# 40Ortho.net
KiCad netlist of a schematic drawn in EAGLE
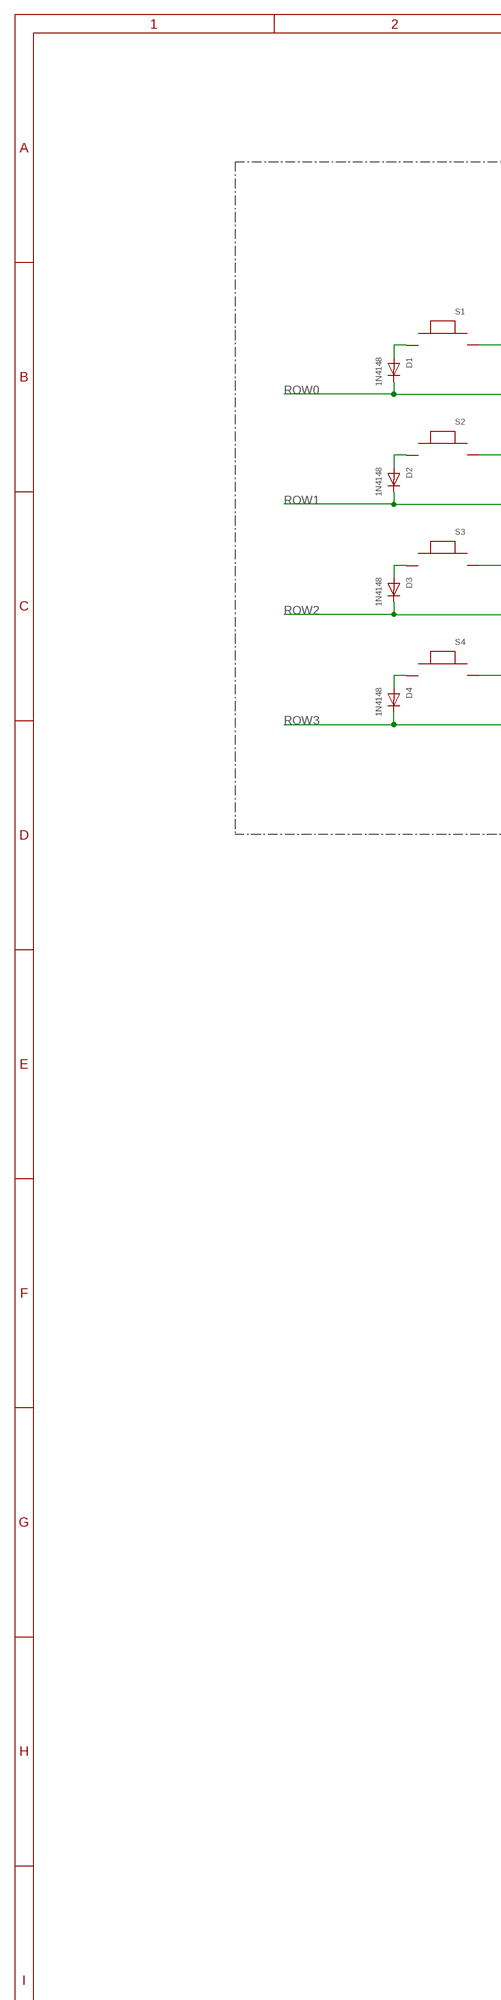
[diagram p0: schematic, sheet 1, part 1 of 2]
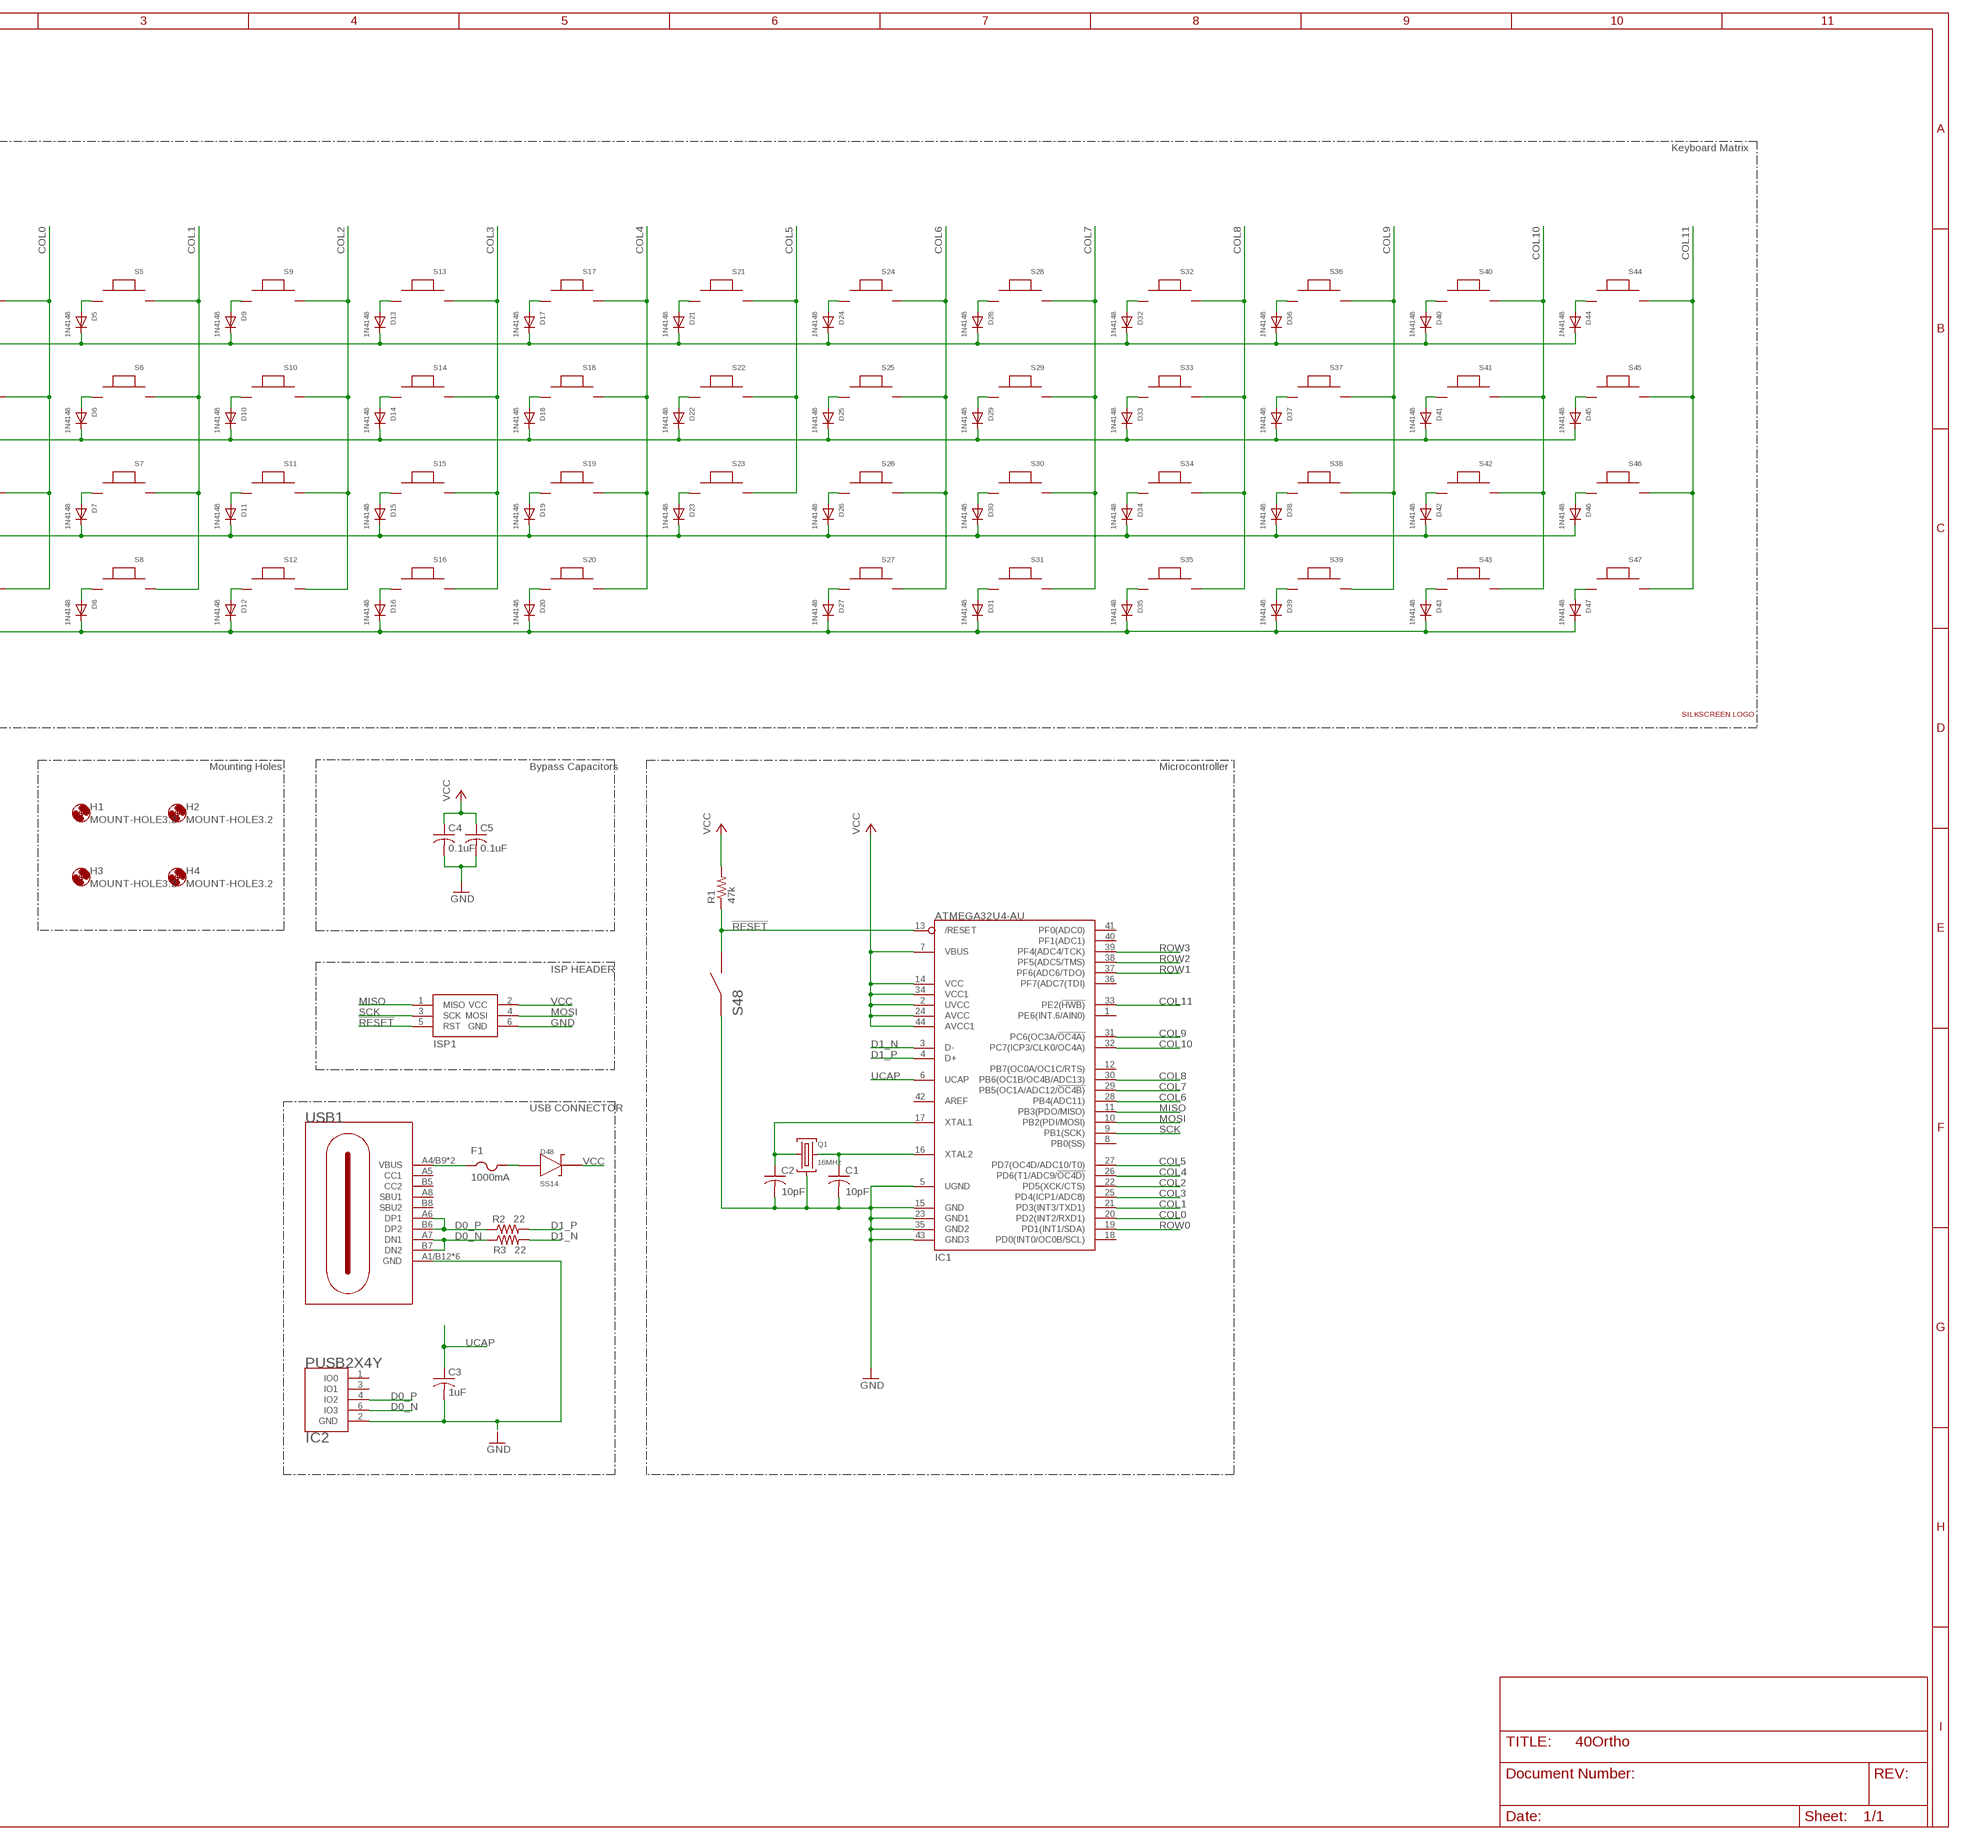
[diagram p1: schematic, sheet 1, part 2 of 2]

(export (version "E")
  (design (tool "Eeschema 10.0.6"))
  (components
    (comp (ref "C1")
      (value "10pF")
      (footprint "eagle-import:C0805")
      (libsource (lib "eagle-import") (part "C-USC0805"))
    )
    (comp (ref "C2")
      (value "10pF")
      (footprint "eagle-import:C0805")
      (libsource (lib "eagle-import") (part "C-USC0805"))
    )
    (comp (ref "C3")
      (value "1uF")
      (footprint "eagle-import:C0805")
      (libsource (lib "eagle-import") (part "C-USC0805"))
    )
    (comp (ref "C4")
      (value "0.1uF")
      (footprint "eagle-import:C0805")
      (libsource (lib "eagle-import") (part "C-USC0805"))
    )
    (comp (ref "C5")
      (value "0.1uF")
      (footprint "eagle-import:C0805")
      (libsource (lib "eagle-import") (part "C-USC0805"))
    )
    (comp (ref "D1")
      (value "1N4148")
      (footprint "eagle-import:SOD-323F")
      (fields (field (name "SPICEPREFIX") "D"))
      (libsource (lib "eagle-import") (part "DIODESOD-323F"))
    )
    (comp (ref "D2")
      (value "1N4148")
      (footprint "eagle-import:SOD-323F")
      (libsource (lib "eagle-import") (part "DIODESOD-323F"))
    )
    (comp (ref "D3")
      (value "1N4148")
      (footprint "eagle-import:SOD-323F")
      (libsource (lib "eagle-import") (part "DIODESOD-323F"))
    )
    (comp (ref "D4")
      (value "1N4148")
      (footprint "eagle-import:SOD-323F")
      (libsource (lib "eagle-import") (part "DIODESOD-323F"))
    )
    (comp (ref "D5")
      (value "1N4148")
      (footprint "eagle-import:SOD-323F")
      (libsource (lib "eagle-import") (part "DIODESOD-323F"))
    )
    (comp (ref "D6")
      (value "1N4148")
      (footprint "eagle-import:SOD-323F")
      (fields (field (name "SPICEPREFIX") "D"))
      (libsource (lib "eagle-import") (part "DIODESOD-323F"))
    )
    (comp (ref "D7")
      (value "1N4148")
      (footprint "eagle-import:SOD-323F")
      (libsource (lib "eagle-import") (part "DIODESOD-323F"))
    )
    (comp (ref "D8")
      (value "1N4148")
      (footprint "eagle-import:SOD-323F")
      (libsource (lib "eagle-import") (part "DIODESOD-323F"))
    )
    (comp (ref "D9")
      (value "1N4148")
      (footprint "eagle-import:SOD-323F")
      (libsource (lib "eagle-import") (part "DIODESOD-323F"))
    )
    (comp (ref "D10")
      (value "1N4148")
      (footprint "eagle-import:SOD-323F")
      (libsource (lib "eagle-import") (part "DIODESOD-323F"))
    )
    (comp (ref "D11")
      (value "1N4148")
      (footprint "eagle-import:SOD-323F")
      (libsource (lib "eagle-import") (part "DIODESOD-323F"))
    )
    (comp (ref "D12")
      (value "1N4148")
      (footprint "eagle-import:SOD-323F")
      (libsource (lib "eagle-import") (part "DIODESOD-323F"))
    )
    (comp (ref "D13")
      (value "1N4148")
      (footprint "eagle-import:SOD-323F")
      (libsource (lib "eagle-import") (part "DIODESOD-323F"))
    )
    (comp (ref "D14")
      (value "1N4148")
      (footprint "eagle-import:SOD-323F")
      (libsource (lib "eagle-import") (part "DIODESOD-323F"))
    )
    (comp (ref "D15")
      (value "1N4148")
      (footprint "eagle-import:SOD-323F")
      (libsource (lib "eagle-import") (part "DIODESOD-323F"))
    )
    (comp (ref "D16")
      (value "1N4148")
      (footprint "eagle-import:SOD-323F")
      (libsource (lib "eagle-import") (part "DIODESOD-323F"))
    )
    (comp (ref "D17")
      (value "1N4148")
      (footprint "eagle-import:SOD-323F")
      (libsource (lib "eagle-import") (part "DIODESOD-323F"))
    )
    (comp (ref "D18")
      (value "1N4148")
      (footprint "eagle-import:SOD-323F")
      (libsource (lib "eagle-import") (part "DIODESOD-323F"))
    )
    (comp (ref "D19")
      (value "1N4148")
      (footprint "eagle-import:SOD-323F")
      (libsource (lib "eagle-import") (part "DIODESOD-323F"))
    )
    (comp (ref "D20")
      (value "1N4148")
      (footprint "eagle-import:SOD-323F")
      (libsource (lib "eagle-import") (part "DIODESOD-323F"))
    )
    (comp (ref "D21")
      (value "1N4148")
      (footprint "eagle-import:SOD-323F")
      (libsource (lib "eagle-import") (part "DIODESOD-323F"))
    )
    (comp (ref "D22")
      (value "1N4148")
      (footprint "eagle-import:SOD-323F")
      (libsource (lib "eagle-import") (part "DIODESOD-323F"))
    )
    (comp (ref "D23")
      (value "1N4148")
      (footprint "eagle-import:SOD-323F")
      (libsource (lib "eagle-import") (part "DIODESOD-323F"))
    )
    (comp (ref "D24")
      (value "1N4148")
      (footprint "eagle-import:SOD-323F")
      (libsource (lib "eagle-import") (part "DIODESOD-323F"))
    )
    (comp (ref "D25")
      (value "1N4148")
      (footprint "eagle-import:SOD-323F")
      (libsource (lib "eagle-import") (part "DIODESOD-323F"))
    )
    (comp (ref "D26")
      (value "1N4148")
      (footprint "eagle-import:SOD-323F")
      (libsource (lib "eagle-import") (part "DIODESOD-323F"))
    )
    (comp (ref "D27")
      (value "1N4148")
      (footprint "eagle-import:SOD-323F")
      (libsource (lib "eagle-import") (part "DIODESOD-323F"))
    )
    (comp (ref "D28")
      (value "1N4148")
      (footprint "eagle-import:SOD-323F")
      (libsource (lib "eagle-import") (part "DIODESOD-323F"))
    )
    (comp (ref "D29")
      (value "1N4148")
      (footprint "eagle-import:SOD-323F")
      (libsource (lib "eagle-import") (part "DIODESOD-323F"))
    )
    (comp (ref "D30")
      (value "1N4148")
      (footprint "eagle-import:SOD-323F")
      (libsource (lib "eagle-import") (part "DIODESOD-323F"))
    )
    (comp (ref "D31")
      (value "1N4148")
      (footprint "eagle-import:SOD-323F")
      (libsource (lib "eagle-import") (part "DIODESOD-323F"))
    )
    (comp (ref "D32")
      (value "1N4148")
      (footprint "eagle-import:SOD-323F")
      (libsource (lib "eagle-import") (part "DIODESOD-323F"))
    )
    (comp (ref "D33")
      (value "1N4148")
      (footprint "eagle-import:SOD-323F")
      (libsource (lib "eagle-import") (part "DIODESOD-323F"))
    )
    (comp (ref "D34")
      (value "1N4148")
      (footprint "eagle-import:SOD-323F")
      (libsource (lib "eagle-import") (part "DIODESOD-323F"))
    )
    (comp (ref "D35")
      (value "1N4148")
      (footprint "eagle-import:SOD-323F")
      (libsource (lib "eagle-import") (part "DIODESOD-323F"))
    )
    (comp (ref "D36")
      (value "1N4148")
      (footprint "eagle-import:SOD-323F")
      (libsource (lib "eagle-import") (part "DIODESOD-323F"))
    )
    (comp (ref "D37")
      (value "1N4148")
      (footprint "eagle-import:SOD-323F")
      (libsource (lib "eagle-import") (part "DIODESOD-323F"))
    )
    (comp (ref "D38")
      (value "1N4148")
      (footprint "eagle-import:SOD-323F")
      (libsource (lib "eagle-import") (part "DIODESOD-323F"))
    )
    (comp (ref "D39")
      (value "1N4148")
      (footprint "eagle-import:SOD-323F")
      (libsource (lib "eagle-import") (part "DIODESOD-323F"))
    )
    (comp (ref "D40")
      (value "1N4148")
      (footprint "eagle-import:SOD-323F")
      (libsource (lib "eagle-import") (part "DIODESOD-323F"))
    )
    (comp (ref "D41")
      (value "1N4148")
      (footprint "eagle-import:SOD-323F")
      (libsource (lib "eagle-import") (part "DIODESOD-323F"))
    )
    (comp (ref "D42")
      (value "1N4148")
      (footprint "eagle-import:SOD-323F")
      (libsource (lib "eagle-import") (part "DIODESOD-323F"))
    )
    (comp (ref "D43")
      (value "1N4148")
      (footprint "eagle-import:SOD-323F")
      (libsource (lib "eagle-import") (part "DIODESOD-323F"))
    )
    (comp (ref "D44")
      (value "1N4148")
      (footprint "eagle-import:SOD-323F")
      (libsource (lib "eagle-import") (part "DIODESOD-323F"))
    )
    (comp (ref "D45")
      (value "1N4148")
      (footprint "eagle-import:SOD-323F")
      (libsource (lib "eagle-import") (part "DIODESOD-323F"))
    )
    (comp (ref "D46")
      (value "1N4148")
      (footprint "eagle-import:SOD-323F")
      (libsource (lib "eagle-import") (part "DIODESOD-323F"))
    )
    (comp (ref "D47")
      (value "1N4148")
      (footprint "eagle-import:SOD-323F")
      (libsource (lib "eagle-import") (part "DIODESOD-323F"))
    )
    (comp (ref "D48")
      (value "SS14")
      (footprint "eagle-import:DO-214AC")
      (libsource (lib "eagle-import") (part "SS14"))
    )
    (comp (ref "F1")
      (value "1000mA")
      (footprint "eagle-import:R1206")
      (libsource (lib "eagle-import") (part "PTCFUSE-1206"))
    )
    (comp (ref "H1")
      (value "MOUNT-HOLE3.2")
      (footprint "eagle-import:3,2")
      (libsource (lib "eagle-import") (part "MOUNT-HOLE3.2"))
    )
    (comp (ref "H2")
      (value "MOUNT-HOLE3.2")
      (footprint "eagle-import:3,2")
      (libsource (lib "eagle-import") (part "MOUNT-HOLE3.2"))
    )
    (comp (ref "H3")
      (value "MOUNT-HOLE3.2")
      (footprint "eagle-import:3,2")
      (libsource (lib "eagle-import") (part "MOUNT-HOLE3.2"))
    )
    (comp (ref "H4")
      (value "MOUNT-HOLE3.2")
      (footprint "eagle-import:3,2")
      (libsource (lib "eagle-import") (part "MOUNT-HOLE3.2"))
    )
    (comp (ref "IC1")
      (value "ATMEGA32U4-AU")
      (footprint "eagle-import:TQFP44")
      (libsource (lib "eagle-import") (part "ATMEGA32U4-AU"))
    )
    (comp (ref "IC2")
      (value "PUSB2X4Y")
      (footprint "eagle-import:SOT363")
      (libsource (lib "eagle-import") (part "PUSB2X4Y"))
    )
    (comp (ref "ISP1")
      (value "AVRISP")
      (footprint "eagle-import:AVRISP")
      (libsource (lib "eagle-import") (part "AVRISP"))
    )
    (comp (ref "Q1")
      (value "16MHz")
      (footprint "eagle-import:TSX-3225")
      (libsource (lib "eagle-import") (part "TSX-3225"))
    )
    (comp (ref "R1")
      (value "47k")
      (footprint "eagle-import:R0805")
      (libsource (lib "eagle-import") (part "R-US_R0805"))
    )
    (comp (ref "R2")
      (value "22")
      (footprint "eagle-import:R0805")
      (libsource (lib "eagle-import") (part "R-US_R0805"))
    )
    (comp (ref "R3")
      (value "22")
      (footprint "eagle-import:R0805")
      (libsource (lib "eagle-import") (part "R-US_R0805"))
    )
    (comp (ref "S1")
      (value "MX_SMD_1U")
      (footprint "eagle-import:MX_SMD")
      (libsource (lib "eagle-import") (part "MX_SMD_1U"))
    )
    (comp (ref "S2")
      (value "MX_SMD_1U")
      (footprint "eagle-import:MX_SMD")
      (libsource (lib "eagle-import") (part "MX_SMD_1U"))
    )
    (comp (ref "S3")
      (value "MX_SMD_1U")
      (footprint "eagle-import:MX_SMD")
      (libsource (lib "eagle-import") (part "MX_SMD_1U"))
    )
    (comp (ref "S4")
      (value "MX_SMD_1U")
      (footprint "eagle-import:MX_SMD")
      (libsource (lib "eagle-import") (part "MX_SMD_1U"))
    )
    (comp (ref "S5")
      (value "MX_SMD_1U")
      (footprint "eagle-import:MX_SMD")
      (libsource (lib "eagle-import") (part "MX_SMD_1U"))
    )
    (comp (ref "S6")
      (value "MX_SMD_1U")
      (footprint "eagle-import:MX_SMD")
      (libsource (lib "eagle-import") (part "MX_SMD_1U"))
    )
    (comp (ref "S7")
      (value "MX_SMD_1U")
      (footprint "eagle-import:MX_SMD")
      (libsource (lib "eagle-import") (part "MX_SMD_1U"))
    )
    (comp (ref "S8")
      (value "MX_SMD_1U")
      (footprint "eagle-import:MX_SMD")
      (libsource (lib "eagle-import") (part "MX_SMD_1U"))
    )
    (comp (ref "S9")
      (value "MX_SMD_1U")
      (footprint "eagle-import:MX_SMD")
      (libsource (lib "eagle-import") (part "MX_SMD_1U"))
    )
    (comp (ref "S10")
      (value "MX_SMD_1U")
      (footprint "eagle-import:MX_SMD")
      (libsource (lib "eagle-import") (part "MX_SMD_1U"))
    )
    (comp (ref "S11")
      (value "MX_SMD_1U")
      (footprint "eagle-import:MX_SMD")
      (libsource (lib "eagle-import") (part "MX_SMD_1U"))
    )
    (comp (ref "S12")
      (value "MX_SMD_1U")
      (footprint "eagle-import:MX_SMD")
      (libsource (lib "eagle-import") (part "MX_SMD_1U"))
    )
    (comp (ref "S13")
      (value "MX_SMD_1U")
      (footprint "eagle-import:MX_SMD")
      (libsource (lib "eagle-import") (part "MX_SMD_1U"))
    )
    (comp (ref "S14")
      (value "MX_SMD_1U")
      (footprint "eagle-import:MX_SMD")
      (libsource (lib "eagle-import") (part "MX_SMD_1U"))
    )
    (comp (ref "S15")
      (value "MX_SMD_1U")
      (footprint "eagle-import:MX_SMD")
      (libsource (lib "eagle-import") (part "MX_SMD_1U"))
    )
    (comp (ref "S16")
      (value "MX_SMD_1U")
      (footprint "eagle-import:MX_SMD")
      (libsource (lib "eagle-import") (part "MX_SMD_1U"))
    )
    (comp (ref "S17")
      (value "MX_SMD_1U")
      (footprint "eagle-import:MX_SMD")
      (libsource (lib "eagle-import") (part "MX_SMD_1U"))
    )
    (comp (ref "S18")
      (value "MX_SMD_1U")
      (footprint "eagle-import:MX_SMD")
      (libsource (lib "eagle-import") (part "MX_SMD_1U"))
    )
    (comp (ref "S19")
      (value "MX_SMD_1U")
      (footprint "eagle-import:MX_SMD")
      (libsource (lib "eagle-import") (part "MX_SMD_1U"))
    )
    (comp (ref "S20")
      (value "MX_SMD_1U")
      (footprint "eagle-import:MX_SMD")
      (libsource (lib "eagle-import") (part "MX_SMD_1U"))
    )
    (comp (ref "S21")
      (value "MX_SMD_1U")
      (footprint "eagle-import:MX_SMD")
      (libsource (lib "eagle-import") (part "MX_SMD_1U"))
    )
    (comp (ref "S22")
      (value "MX_SMD_1U")
      (footprint "eagle-import:MX_SMD")
      (libsource (lib "eagle-import") (part "MX_SMD_1U"))
    )
    (comp (ref "S23")
      (value "MX_SMD_1U")
      (footprint "eagle-import:MX_SMD")
      (libsource (lib "eagle-import") (part "MX_SMD_1U"))
    )
    (comp (ref "S24")
      (value "MX_SMD_1U")
      (footprint "eagle-import:MX_SMD")
      (libsource (lib "eagle-import") (part "MX_SMD_1U"))
    )
    (comp (ref "S25")
      (value "MX_SMD_1U")
      (footprint "eagle-import:MX_SMD")
      (libsource (lib "eagle-import") (part "MX_SMD_1U"))
    )
    (comp (ref "S26")
      (value "MX_SMD_1U")
      (footprint "eagle-import:MX_SMD")
      (libsource (lib "eagle-import") (part "MX_SMD_1U"))
    )
    (comp (ref "S27")
      (value "MX_SMD_2UH")
      (footprint "eagle-import:MX_SMD2U")
      (libsource (lib "eagle-import") (part "MX_SMD_2UH"))
    )
    (comp (ref "S28")
      (value "MX_SMD_1U")
      (footprint "eagle-import:MX_SMD")
      (libsource (lib "eagle-import") (part "MX_SMD_1U"))
    )
    (comp (ref "S29")
      (value "MX_SMD_1U")
      (footprint "eagle-import:MX_SMD")
      (libsource (lib "eagle-import") (part "MX_SMD_1U"))
    )
    (comp (ref "S30")
      (value "MX_SMD_1U")
      (footprint "eagle-import:MX_SMD")
      (libsource (lib "eagle-import") (part "MX_SMD_1U"))
    )
    (comp (ref "S31")
      (value "MX_SMD_1U")
      (footprint "eagle-import:MX_SMD")
      (libsource (lib "eagle-import") (part "MX_SMD_1U"))
    )
    (comp (ref "S32")
      (value "MX_SMD_1U")
      (footprint "eagle-import:MX_SMD")
      (libsource (lib "eagle-import") (part "MX_SMD_1U"))
    )
    (comp (ref "S33")
      (value "MX_SMD_1U")
      (footprint "eagle-import:MX_SMD")
      (libsource (lib "eagle-import") (part "MX_SMD_1U"))
    )
    (comp (ref "S34")
      (value "MX_SMD_1U")
      (footprint "eagle-import:MX_SMD")
      (libsource (lib "eagle-import") (part "MX_SMD_1U"))
    )
    (comp (ref "S35")
      (value "MX_SMD_1U")
      (footprint "eagle-import:MX_SMD")
      (libsource (lib "eagle-import") (part "MX_SMD_1U"))
    )
    (comp (ref "S36")
      (value "MX_SMD_1U")
      (footprint "eagle-import:MX_SMD")
      (libsource (lib "eagle-import") (part "MX_SMD_1U"))
    )
    (comp (ref "S37")
      (value "MX_SMD_1U")
      (footprint "eagle-import:MX_SMD")
      (libsource (lib "eagle-import") (part "MX_SMD_1U"))
    )
    (comp (ref "S38")
      (value "MX_SMD_1U")
      (footprint "eagle-import:MX_SMD")
      (libsource (lib "eagle-import") (part "MX_SMD_1U"))
    )
    (comp (ref "S39")
      (value "MX_SMD_1U")
      (footprint "eagle-import:MX_SMD")
      (libsource (lib "eagle-import") (part "MX_SMD_1U"))
    )
    (comp (ref "S40")
      (value "MX_SMD_1U")
      (footprint "eagle-import:MX_SMD")
      (libsource (lib "eagle-import") (part "MX_SMD_1U"))
    )
    (comp (ref "S41")
      (value "MX_SMD_1U")
      (footprint "eagle-import:MX_SMD")
      (libsource (lib "eagle-import") (part "MX_SMD_1U"))
    )
    (comp (ref "S42")
      (value "MX_SMD_1U")
      (footprint "eagle-import:MX_SMD")
      (libsource (lib "eagle-import") (part "MX_SMD_1U"))
    )
    (comp (ref "S43")
      (value "MX_SMD_1U")
      (footprint "eagle-import:MX_SMD")
      (libsource (lib "eagle-import") (part "MX_SMD_1U"))
    )
    (comp (ref "S44")
      (value "MX_SMD_1U")
      (footprint "eagle-import:MX_SMD")
      (libsource (lib "eagle-import") (part "MX_SMD_1U"))
    )
    (comp (ref "S45")
      (value "MX_SMD_1U")
      (footprint "eagle-import:MX_SMD")
      (libsource (lib "eagle-import") (part "MX_SMD_1U"))
    )
    (comp (ref "S46")
      (value "MX_SMD_1U")
      (footprint "eagle-import:MX_SMD")
      (libsource (lib "eagle-import") (part "MX_SMD_1U"))
    )
    (comp (ref "S47")
      (value "MX_SMD_1U")
      (footprint "eagle-import:MX_SMD")
      (libsource (lib "eagle-import") (part "MX_SMD_1U"))
    )
    (comp (ref "S48")
      (value "B3U-1000P")
      (footprint "eagle-import:B3U-1000P")
      (libsource (lib "eagle-import") (part "B3U-1000P"))
    )
    (comp (ref "U$1")
      (value "LOGO")
      (footprint "eagle-import:LOGO")
      (libsource (lib "eagle-import") (part "LOGO"))
    )
    (comp (ref "USB1")
      (value "USBC_16PINSMD")
      (footprint "eagle-import:USBC_16PINSMD")
      (libsource (lib "eagle-import") (part "USBC_16PINSMD"))
    )
  )
  (nets
    (net (code "1") (name "/COL0") (class "Default")
      (node (ref "IC1") (pin "20") (pinfunction "PD2(INT2/RXD1)_20") (pintype "bidirectional"))
      (node (ref "S1") (pin "P$2") (pinfunction "P$2_P$2") (pintype "bidirectional"))
      (node (ref "S2") (pin "P$2") (pinfunction "P$2_P$2") (pintype "bidirectional"))
      (node (ref "S3") (pin "P$2") (pinfunction "P$2_P$2") (pintype "bidirectional"))
      (node (ref "S4") (pin "P$2") (pinfunction "P$2_P$2") (pintype "bidirectional"))
    )
    (net (code "2") (name "/COL1") (class "Default")
      (node (ref "IC1") (pin "21") (pinfunction "PD3(INT3/TXD1)_21") (pintype "bidirectional"))
      (node (ref "S5") (pin "P$2") (pinfunction "P$2_P$2") (pintype "bidirectional"))
      (node (ref "S6") (pin "P$2") (pinfunction "P$2_P$2") (pintype "bidirectional"))
      (node (ref "S7") (pin "P$2") (pinfunction "P$2_P$2") (pintype "bidirectional"))
      (node (ref "S8") (pin "P$2") (pinfunction "P$2_P$2") (pintype "bidirectional"))
    )
    (net (code "3") (name "/COL2") (class "Default")
      (node (ref "IC1") (pin "22") (pinfunction "PD5(XCK/CTS)_22") (pintype "bidirectional"))
      (node (ref "S10") (pin "P$2") (pinfunction "P$2_P$2") (pintype "bidirectional"))
      (node (ref "S11") (pin "P$2") (pinfunction "P$2_P$2") (pintype "bidirectional"))
      (node (ref "S12") (pin "P$2") (pinfunction "P$2_P$2") (pintype "bidirectional"))
      (node (ref "S9") (pin "P$2") (pinfunction "P$2_P$2") (pintype "bidirectional"))
    )
    (net (code "4") (name "/COL3") (class "Default")
      (node (ref "IC1") (pin "25") (pinfunction "PD4(ICP1/ADC8)_25") (pintype "bidirectional"))
      (node (ref "S13") (pin "P$2") (pinfunction "P$2_P$2") (pintype "bidirectional"))
      (node (ref "S14") (pin "P$2") (pinfunction "P$2_P$2") (pintype "bidirectional"))
      (node (ref "S15") (pin "P$2") (pinfunction "P$2_P$2") (pintype "bidirectional"))
      (node (ref "S16") (pin "P$2") (pinfunction "P$2_P$2") (pintype "bidirectional"))
    )
    (net (code "5") (name "/COL4") (class "Default")
      (node (ref "IC1") (pin "26") (pinfunction "PD6(T1/ADC9/~{OC4D})_26") (pintype "bidirectional"))
      (node (ref "S17") (pin "P$2") (pinfunction "P$2_P$2") (pintype "bidirectional"))
      (node (ref "S18") (pin "P$2") (pinfunction "P$2_P$2") (pintype "bidirectional"))
      (node (ref "S19") (pin "P$2") (pinfunction "P$2_P$2") (pintype "bidirectional"))
      (node (ref "S20") (pin "P$2") (pinfunction "P$2_P$2") (pintype "bidirectional"))
    )
    (net (code "6") (name "/COL5") (class "Default")
      (node (ref "IC1") (pin "27") (pinfunction "PD7(OC4D/ADC10/T0)_27") (pintype "bidirectional"))
      (node (ref "S21") (pin "P$2") (pinfunction "P$2_P$2") (pintype "bidirectional"))
      (node (ref "S22") (pin "P$2") (pinfunction "P$2_P$2") (pintype "bidirectional"))
      (node (ref "S23") (pin "P$2") (pinfunction "P$2_P$2") (pintype "bidirectional"))
    )
    (net (code "7") (name "/COL6") (class "Default")
      (node (ref "IC1") (pin "28") (pinfunction "PB4(ADC11)_28") (pintype "bidirectional"))
      (node (ref "S24") (pin "P$2") (pinfunction "P$2_P$2") (pintype "bidirectional"))
      (node (ref "S25") (pin "P$2") (pinfunction "P$2_P$2") (pintype "bidirectional"))
      (node (ref "S26") (pin "P$2") (pinfunction "P$2_P$2") (pintype "bidirectional"))
      (node (ref "S27") (pin "P$2") (pinfunction "P$2_P$2") (pintype "bidirectional"))
    )
    (net (code "8") (name "/COL7") (class "Default")
      (node (ref "IC1") (pin "29") (pinfunction "PB5(OC1A/ADC12/~{OC4B})_29") (pintype "bidirectional"))
      (node (ref "S28") (pin "P$2") (pinfunction "P$2_P$2") (pintype "bidirectional"))
      (node (ref "S29") (pin "P$2") (pinfunction "P$2_P$2") (pintype "bidirectional"))
      (node (ref "S30") (pin "P$2") (pinfunction "P$2_P$2") (pintype "bidirectional"))
      (node (ref "S31") (pin "P$2") (pinfunction "P$2_P$2") (pintype "bidirectional"))
    )
    (net (code "9") (name "/COL8") (class "Default")
      (node (ref "IC1") (pin "30") (pinfunction "PB6(OC1B/OC4B/ADC13)_30") (pintype "bidirectional"))
      (node (ref "S32") (pin "P$2") (pinfunction "P$2_P$2") (pintype "bidirectional"))
      (node (ref "S33") (pin "P$2") (pinfunction "P$2_P$2") (pintype "bidirectional"))
      (node (ref "S34") (pin "P$2") (pinfunction "P$2_P$2") (pintype "bidirectional"))
      (node (ref "S35") (pin "P$2") (pinfunction "P$2_P$2") (pintype "bidirectional"))
    )
    (net (code "10") (name "/COL9") (class "Default")
      (node (ref "IC1") (pin "31") (pinfunction "PC6(OC3A/~{OC4A})_31") (pintype "bidirectional"))
      (node (ref "S36") (pin "P$2") (pinfunction "P$2_P$2") (pintype "bidirectional"))
      (node (ref "S37") (pin "P$2") (pinfunction "P$2_P$2") (pintype "bidirectional"))
      (node (ref "S38") (pin "P$2") (pinfunction "P$2_P$2") (pintype "bidirectional"))
      (node (ref "S39") (pin "P$2") (pinfunction "P$2_P$2") (pintype "bidirectional"))
    )
    (net (code "11") (name "/COL10") (class "Default")
      (node (ref "IC1") (pin "32") (pinfunction "PC7(ICP3/CLK0/OC4A)_32") (pintype "bidirectional"))
      (node (ref "S40") (pin "P$2") (pinfunction "P$2_P$2") (pintype "bidirectional"))
      (node (ref "S41") (pin "P$2") (pinfunction "P$2_P$2") (pintype "bidirectional"))
      (node (ref "S42") (pin "P$2") (pinfunction "P$2_P$2") (pintype "bidirectional"))
      (node (ref "S43") (pin "P$2") (pinfunction "P$2_P$2") (pintype "bidirectional"))
    )
    (net (code "12") (name "/COL11") (class "Default")
      (node (ref "IC1") (pin "33") (pinfunction "PE2(~{HWB})_33") (pintype "bidirectional"))
      (node (ref "S44") (pin "P$2") (pinfunction "P$2_P$2") (pintype "bidirectional"))
      (node (ref "S45") (pin "P$2") (pinfunction "P$2_P$2") (pintype "bidirectional"))
      (node (ref "S46") (pin "P$2") (pinfunction "P$2_P$2") (pintype "bidirectional"))
      (node (ref "S47") (pin "P$2") (pinfunction "P$2_P$2") (pintype "bidirectional"))
    )
    (net (code "13") (name "/D0_N") (class "Default")
      (node (ref "IC2") (pin "6") (pinfunction "IO3_6") (pintype "bidirectional"))
      (node (ref "R3") (pin "1") (pinfunction "1_1") (pintype "passive"))
      (node (ref "USB1") (pin "A7") (pinfunction "DN1_A7") (pintype "bidirectional"))
      (node (ref "USB1") (pin "B7") (pinfunction "DN2_B7") (pintype "bidirectional"))
    )
    (net (code "14") (name "/D0_P") (class "Default")
      (node (ref "IC2") (pin "4") (pinfunction "IO2_4") (pintype "bidirectional"))
      (node (ref "R2") (pin "1") (pinfunction "1_1") (pintype "passive"))
      (node (ref "USB1") (pin "A6") (pinfunction "DP1_A6") (pintype "bidirectional"))
      (node (ref "USB1") (pin "B6") (pinfunction "DP2_B6") (pintype "bidirectional"))
    )
    (net (code "15") (name "/D1_N") (class "Default")
      (node (ref "IC1") (pin "3") (pinfunction "D-_3") (pintype "bidirectional"))
      (node (ref "R3") (pin "2") (pinfunction "2_2") (pintype "passive"))
    )
    (net (code "16") (name "/D1_P") (class "Default")
      (node (ref "IC1") (pin "4") (pinfunction "D+_4") (pintype "bidirectional"))
      (node (ref "R2") (pin "2") (pinfunction "2_2") (pintype "passive"))
    )
    (net (code "17") (name "/MISO") (class "Default")
      (node (ref "IC1") (pin "11") (pinfunction "PB3(PDO/MISO)_11") (pintype "bidirectional"))
      (node (ref "ISP1") (pin "1") (pinfunction "MISO_1") (pintype "bidirectional"))
    )
    (net (code "18") (name "/MOSI") (class "Default")
      (node (ref "IC1") (pin "10") (pinfunction "PB2(PDI/MOSI)_10") (pintype "bidirectional"))
      (node (ref "ISP1") (pin "4") (pinfunction "MOSI_4") (pintype "bidirectional"))
    )
    (net (code "19") (name "/ROW0") (class "Default")
      (node (ref "D1") (pin "C") (pinfunction "C_C") (pintype "passive"))
      (node (ref "D13") (pin "C") (pinfunction "C_C") (pintype "passive"))
      (node (ref "D17") (pin "C") (pinfunction "C_C") (pintype "passive"))
      (node (ref "D21") (pin "C") (pinfunction "C_C") (pintype "passive"))
      (node (ref "D24") (pin "C") (pinfunction "C_C") (pintype "passive"))
      (node (ref "D28") (pin "C") (pinfunction "C_C") (pintype "passive"))
      (node (ref "D32") (pin "C") (pinfunction "C_C") (pintype "passive"))
      (node (ref "D36") (pin "C") (pinfunction "C_C") (pintype "passive"))
      (node (ref "D40") (pin "C") (pinfunction "C_C") (pintype "passive"))
      (node (ref "D44") (pin "C") (pinfunction "C_C") (pintype "passive"))
      (node (ref "D5") (pin "C") (pinfunction "C_C") (pintype "passive"))
      (node (ref "D9") (pin "C") (pinfunction "C_C") (pintype "passive"))
      (node (ref "IC1") (pin "19") (pinfunction "PD1(INT1/SDA)_19") (pintype "bidirectional"))
    )
    (net (code "20") (name "/ROW1") (class "Default")
      (node (ref "D10") (pin "C") (pinfunction "C_C") (pintype "passive"))
      (node (ref "D14") (pin "C") (pinfunction "C_C") (pintype "passive"))
      (node (ref "D18") (pin "C") (pinfunction "C_C") (pintype "passive"))
      (node (ref "D2") (pin "C") (pinfunction "C_C") (pintype "passive"))
      (node (ref "D22") (pin "C") (pinfunction "C_C") (pintype "passive"))
      (node (ref "D25") (pin "C") (pinfunction "C_C") (pintype "passive"))
      (node (ref "D29") (pin "C") (pinfunction "C_C") (pintype "passive"))
      (node (ref "D33") (pin "C") (pinfunction "C_C") (pintype "passive"))
      (node (ref "D37") (pin "C") (pinfunction "C_C") (pintype "passive"))
      (node (ref "D41") (pin "C") (pinfunction "C_C") (pintype "passive"))
      (node (ref "D45") (pin "C") (pinfunction "C_C") (pintype "passive"))
      (node (ref "D6") (pin "C") (pinfunction "C_C") (pintype "passive"))
      (node (ref "IC1") (pin "37") (pinfunction "PF6(ADC6/TDO)_37") (pintype "bidirectional"))
    )
    (net (code "21") (name "/ROW2") (class "Default")
      (node (ref "D11") (pin "C") (pinfunction "C_C") (pintype "passive"))
      (node (ref "D15") (pin "C") (pinfunction "C_C") (pintype "passive"))
      (node (ref "D19") (pin "C") (pinfunction "C_C") (pintype "passive"))
      (node (ref "D23") (pin "C") (pinfunction "C_C") (pintype "passive"))
      (node (ref "D26") (pin "C") (pinfunction "C_C") (pintype "passive"))
      (node (ref "D3") (pin "C") (pinfunction "C_C") (pintype "passive"))
      (node (ref "D30") (pin "C") (pinfunction "C_C") (pintype "passive"))
      (node (ref "D34") (pin "C") (pinfunction "C_C") (pintype "passive"))
      (node (ref "D38") (pin "C") (pinfunction "C_C") (pintype "passive"))
      (node (ref "D42") (pin "C") (pinfunction "C_C") (pintype "passive"))
      (node (ref "D46") (pin "C") (pinfunction "C_C") (pintype "passive"))
      (node (ref "D7") (pin "C") (pinfunction "C_C") (pintype "passive"))
      (node (ref "IC1") (pin "38") (pinfunction "PF5(ADC5/TMS)_38") (pintype "bidirectional"))
    )
    (net (code "22") (name "/ROW3") (class "Default")
      (node (ref "D12") (pin "C") (pinfunction "C_C") (pintype "passive"))
      (node (ref "D16") (pin "C") (pinfunction "C_C") (pintype "passive"))
      (node (ref "D20") (pin "C") (pinfunction "C_C") (pintype "passive"))
      (node (ref "D27") (pin "C") (pinfunction "C_C") (pintype "passive"))
      (node (ref "D31") (pin "C") (pinfunction "C_C") (pintype "passive"))
      (node (ref "D35") (pin "C") (pinfunction "C_C") (pintype "passive"))
      (node (ref "D39") (pin "C") (pinfunction "C_C") (pintype "passive"))
      (node (ref "D4") (pin "C") (pinfunction "C_C") (pintype "passive"))
      (node (ref "D43") (pin "C") (pinfunction "C_C") (pintype "passive"))
      (node (ref "D47") (pin "C") (pinfunction "C_C") (pintype "passive"))
      (node (ref "D8") (pin "C") (pinfunction "C_C") (pintype "passive"))
      (node (ref "IC1") (pin "39") (pinfunction "PF4(ADC4/TCK)_39") (pintype "bidirectional"))
    )
    (net (code "23") (name "/SCK") (class "Default")
      (node (ref "IC1") (pin "9") (pinfunction "PB1(SCK)_9") (pintype "bidirectional"))
      (node (ref "ISP1") (pin "3") (pinfunction "SCK_3") (pintype "bidirectional"))
    )
    (net (code "24") (name "/UCAP") (class "Default")
      (node (ref "C3") (pin "1") (pinfunction "1_1") (pintype "passive"))
      (node (ref "IC1") (pin "6") (pinfunction "UCAP_6") (pintype "bidirectional"))
    )
    (net (code "25") (name "/~{RESET}") (class "Default")
      (node (ref "IC1") (pin "13") (pinfunction "/RESET_13") (pintype "bidirectional"))
      (node (ref "ISP1") (pin "5") (pinfunction "RST_5") (pintype "bidirectional"))
      (node (ref "R1") (pin "1") (pinfunction "1_1") (pintype "passive"))
      (node (ref "S48") (pin "2") (pinfunction "P$2_2") (pintype "bidirectional"))
    )
    (net (code "26") (name "GND") (class "Default")
      (node (ref "C1") (pin "2") (pinfunction "2_2") (pintype "passive"))
      (node (ref "C2") (pin "2") (pinfunction "2_2") (pintype "passive"))
      (node (ref "C3") (pin "2") (pinfunction "2_2") (pintype "passive"))
      (node (ref "C4") (pin "2") (pinfunction "2_2") (pintype "passive"))
      (node (ref "C5") (pin "2") (pinfunction "2_2") (pintype "passive"))
      (node (ref "IC1") (pin "15") (pinfunction "GND_15") (pintype "bidirectional"))
      (node (ref "IC1") (pin "23") (pinfunction "GND1_23") (pintype "bidirectional"))
      (node (ref "IC1") (pin "35") (pinfunction "GND2_35") (pintype "bidirectional"))
      (node (ref "IC1") (pin "43") (pinfunction "GND3_43") (pintype "bidirectional"))
      (node (ref "IC1") (pin "5") (pinfunction "UGND_5") (pintype "bidirectional"))
      (node (ref "IC2") (pin "2") (pinfunction "GND_2") (pintype "power_in"))
      (node (ref "ISP1") (pin "6") (pinfunction "GND_6") (pintype "bidirectional"))
      (node (ref "Q1") (pin "2") (pinfunction "CVR_2") (pintype "passive"))
      (node (ref "Q1") (pin "4") (pinfunction "CVR_4") (pintype "passive"))
      (node (ref "S48") (pin "1") (pinfunction "P$1_1") (pintype "bidirectional"))
      (node (ref "USB1") (pin "A1/B12") (pinfunction "GND_A1/B12") (pintype "power_in"))
      (node (ref "USB1") (pin "B1/A12") (pinfunction "GND_B1/A12") (pintype "power_in"))
      (node (ref "USB1") (pin "GND@1") (pinfunction "GND_GND@1") (pintype "power_in"))
      (node (ref "USB1") (pin "GND@2") (pinfunction "GND_GND@2") (pintype "power_in"))
      (node (ref "USB1") (pin "GND@3") (pinfunction "GND_GND@3") (pintype "power_in"))
      (node (ref "USB1") (pin "GND@4") (pinfunction "GND_GND@4") (pintype "power_in"))
    )
    (net (code "27") (name "Net-(D1-PadA)") (class "Default")
      (node (ref "D1") (pin "A") (pinfunction "A_A") (pintype "passive"))
      (node (ref "S1") (pin "P$1") (pinfunction "P$1_P$1") (pintype "bidirectional"))
    )
    (net (code "28") (name "Net-(D2-PadA)") (class "Default")
      (node (ref "D2") (pin "A") (pinfunction "A_A") (pintype "passive"))
      (node (ref "S2") (pin "P$1") (pinfunction "P$1_P$1") (pintype "bidirectional"))
    )
    (net (code "29") (name "Net-(D3-PadA)") (class "Default")
      (node (ref "D3") (pin "A") (pinfunction "A_A") (pintype "passive"))
      (node (ref "S3") (pin "P$1") (pinfunction "P$1_P$1") (pintype "bidirectional"))
    )
    (net (code "30") (name "Net-(D4-PadA)") (class "Default")
      (node (ref "D4") (pin "A") (pinfunction "A_A") (pintype "passive"))
      (node (ref "S4") (pin "P$1") (pinfunction "P$1_P$1") (pintype "bidirectional"))
    )
    (net (code "31") (name "Net-(D5-PadA)") (class "Default")
      (node (ref "D5") (pin "A") (pinfunction "A_A") (pintype "passive"))
      (node (ref "S5") (pin "P$1") (pinfunction "P$1_P$1") (pintype "bidirectional"))
    )
    (net (code "32") (name "Net-(D6-PadA)") (class "Default")
      (node (ref "D6") (pin "A") (pinfunction "A_A") (pintype "passive"))
      (node (ref "S6") (pin "P$1") (pinfunction "P$1_P$1") (pintype "bidirectional"))
    )
    (net (code "33") (name "Net-(D7-PadA)") (class "Default")
      (node (ref "D7") (pin "A") (pinfunction "A_A") (pintype "passive"))
      (node (ref "S7") (pin "P$1") (pinfunction "P$1_P$1") (pintype "bidirectional"))
    )
    (net (code "34") (name "Net-(D8-PadA)") (class "Default")
      (node (ref "D8") (pin "A") (pinfunction "A_A") (pintype "passive"))
      (node (ref "S8") (pin "P$1") (pinfunction "P$1_P$1") (pintype "bidirectional"))
    )
    (net (code "35") (name "Net-(D9-PadA)") (class "Default")
      (node (ref "D9") (pin "A") (pinfunction "A_A") (pintype "passive"))
      (node (ref "S9") (pin "P$1") (pinfunction "P$1_P$1") (pintype "bidirectional"))
    )
    (net (code "36") (name "Net-(D10-PadA)") (class "Default")
      (node (ref "D10") (pin "A") (pinfunction "A_A") (pintype "passive"))
      (node (ref "S10") (pin "P$1") (pinfunction "P$1_P$1") (pintype "bidirectional"))
    )
    (net (code "37") (name "Net-(D11-PadA)") (class "Default")
      (node (ref "D11") (pin "A") (pinfunction "A_A") (pintype "passive"))
      (node (ref "S11") (pin "P$1") (pinfunction "P$1_P$1") (pintype "bidirectional"))
    )
    (net (code "38") (name "Net-(D12-PadA)") (class "Default")
      (node (ref "D12") (pin "A") (pinfunction "A_A") (pintype "passive"))
      (node (ref "S12") (pin "P$1") (pinfunction "P$1_P$1") (pintype "bidirectional"))
    )
    (net (code "39") (name "Net-(D13-PadA)") (class "Default")
      (node (ref "D13") (pin "A") (pinfunction "A_A") (pintype "passive"))
      (node (ref "S13") (pin "P$1") (pinfunction "P$1_P$1") (pintype "bidirectional"))
    )
    (net (code "40") (name "Net-(D14-PadA)") (class "Default")
      (node (ref "D14") (pin "A") (pinfunction "A_A") (pintype "passive"))
      (node (ref "S14") (pin "P$1") (pinfunction "P$1_P$1") (pintype "bidirectional"))
    )
    (net (code "41") (name "Net-(D15-PadA)") (class "Default")
      (node (ref "D15") (pin "A") (pinfunction "A_A") (pintype "passive"))
      (node (ref "S15") (pin "P$1") (pinfunction "P$1_P$1") (pintype "bidirectional"))
    )
    (net (code "42") (name "Net-(D16-PadA)") (class "Default")
      (node (ref "D16") (pin "A") (pinfunction "A_A") (pintype "passive"))
      (node (ref "S16") (pin "P$1") (pinfunction "P$1_P$1") (pintype "bidirectional"))
    )
    (net (code "43") (name "Net-(D17-PadA)") (class "Default")
      (node (ref "D17") (pin "A") (pinfunction "A_A") (pintype "passive"))
      (node (ref "S17") (pin "P$1") (pinfunction "P$1_P$1") (pintype "bidirectional"))
    )
    (net (code "44") (name "Net-(D18-PadA)") (class "Default")
      (node (ref "D18") (pin "A") (pinfunction "A_A") (pintype "passive"))
      (node (ref "S18") (pin "P$1") (pinfunction "P$1_P$1") (pintype "bidirectional"))
    )
    (net (code "45") (name "Net-(D19-PadA)") (class "Default")
      (node (ref "D19") (pin "A") (pinfunction "A_A") (pintype "passive"))
      (node (ref "S19") (pin "P$1") (pinfunction "P$1_P$1") (pintype "bidirectional"))
    )
    (net (code "46") (name "Net-(D20-PadA)") (class "Default")
      (node (ref "D20") (pin "A") (pinfunction "A_A") (pintype "passive"))
      (node (ref "S20") (pin "P$1") (pinfunction "P$1_P$1") (pintype "bidirectional"))
    )
    (net (code "47") (name "Net-(D21-PadA)") (class "Default")
      (node (ref "D21") (pin "A") (pinfunction "A_A") (pintype "passive"))
      (node (ref "S21") (pin "P$1") (pinfunction "P$1_P$1") (pintype "bidirectional"))
    )
    (net (code "48") (name "Net-(D22-PadA)") (class "Default")
      (node (ref "D22") (pin "A") (pinfunction "A_A") (pintype "passive"))
      (node (ref "S22") (pin "P$1") (pinfunction "P$1_P$1") (pintype "bidirectional"))
    )
    (net (code "49") (name "Net-(D23-PadA)") (class "Default")
      (node (ref "D23") (pin "A") (pinfunction "A_A") (pintype "passive"))
      (node (ref "S23") (pin "P$1") (pinfunction "P$1_P$1") (pintype "bidirectional"))
    )
    (net (code "50") (name "Net-(D24-PadA)") (class "Default")
      (node (ref "D24") (pin "A") (pinfunction "A_A") (pintype "passive"))
      (node (ref "S24") (pin "P$1") (pinfunction "P$1_P$1") (pintype "bidirectional"))
    )
    (net (code "51") (name "Net-(D25-PadA)") (class "Default")
      (node (ref "D25") (pin "A") (pinfunction "A_A") (pintype "passive"))
      (node (ref "S25") (pin "P$1") (pinfunction "P$1_P$1") (pintype "bidirectional"))
    )
    (net (code "52") (name "Net-(D26-PadA)") (class "Default")
      (node (ref "D26") (pin "A") (pinfunction "A_A") (pintype "passive"))
      (node (ref "S26") (pin "P$1") (pinfunction "P$1_P$1") (pintype "bidirectional"))
    )
    (net (code "53") (name "Net-(D27-PadA)") (class "Default")
      (node (ref "D27") (pin "A") (pinfunction "A_A") (pintype "passive"))
      (node (ref "S27") (pin "P$1") (pinfunction "P$1_P$1") (pintype "bidirectional"))
    )
    (net (code "54") (name "Net-(D28-PadA)") (class "Default")
      (node (ref "D28") (pin "A") (pinfunction "A_A") (pintype "passive"))
      (node (ref "S28") (pin "P$1") (pinfunction "P$1_P$1") (pintype "bidirectional"))
    )
    (net (code "55") (name "Net-(D29-PadA)") (class "Default")
      (node (ref "D29") (pin "A") (pinfunction "A_A") (pintype "passive"))
      (node (ref "S29") (pin "P$1") (pinfunction "P$1_P$1") (pintype "bidirectional"))
    )
    (net (code "56") (name "Net-(D30-PadA)") (class "Default")
      (node (ref "D30") (pin "A") (pinfunction "A_A") (pintype "passive"))
      (node (ref "S30") (pin "P$1") (pinfunction "P$1_P$1") (pintype "bidirectional"))
    )
    (net (code "57") (name "Net-(D31-PadA)") (class "Default")
      (node (ref "D31") (pin "A") (pinfunction "A_A") (pintype "passive"))
      (node (ref "S31") (pin "P$1") (pinfunction "P$1_P$1") (pintype "bidirectional"))
    )
    (net (code "58") (name "Net-(D32-PadA)") (class "Default")
      (node (ref "D32") (pin "A") (pinfunction "A_A") (pintype "passive"))
      (node (ref "S32") (pin "P$1") (pinfunction "P$1_P$1") (pintype "bidirectional"))
    )
    (net (code "59") (name "Net-(D33-PadA)") (class "Default")
      (node (ref "D33") (pin "A") (pinfunction "A_A") (pintype "passive"))
      (node (ref "S33") (pin "P$1") (pinfunction "P$1_P$1") (pintype "bidirectional"))
    )
    (net (code "60") (name "Net-(D34-PadA)") (class "Default")
      (node (ref "D34") (pin "A") (pinfunction "A_A") (pintype "passive"))
      (node (ref "S34") (pin "P$1") (pinfunction "P$1_P$1") (pintype "bidirectional"))
    )
    (net (code "61") (name "Net-(D35-PadA)") (class "Default")
      (node (ref "D35") (pin "A") (pinfunction "A_A") (pintype "passive"))
      (node (ref "S35") (pin "P$1") (pinfunction "P$1_P$1") (pintype "bidirectional"))
    )
    (net (code "62") (name "Net-(D36-PadA)") (class "Default")
      (node (ref "D36") (pin "A") (pinfunction "A_A") (pintype "passive"))
      (node (ref "S36") (pin "P$1") (pinfunction "P$1_P$1") (pintype "bidirectional"))
    )
    (net (code "63") (name "Net-(D37-PadA)") (class "Default")
      (node (ref "D37") (pin "A") (pinfunction "A_A") (pintype "passive"))
      (node (ref "S37") (pin "P$1") (pinfunction "P$1_P$1") (pintype "bidirectional"))
    )
    (net (code "64") (name "Net-(D38-PadA)") (class "Default")
      (node (ref "D38") (pin "A") (pinfunction "A_A") (pintype "passive"))
      (node (ref "S38") (pin "P$1") (pinfunction "P$1_P$1") (pintype "bidirectional"))
    )
    (net (code "65") (name "Net-(D39-PadA)") (class "Default")
      (node (ref "D39") (pin "A") (pinfunction "A_A") (pintype "passive"))
      (node (ref "S39") (pin "P$1") (pinfunction "P$1_P$1") (pintype "bidirectional"))
    )
    (net (code "66") (name "Net-(D40-PadA)") (class "Default")
      (node (ref "D40") (pin "A") (pinfunction "A_A") (pintype "passive"))
      (node (ref "S40") (pin "P$1") (pinfunction "P$1_P$1") (pintype "bidirectional"))
    )
    (net (code "67") (name "Net-(D41-PadA)") (class "Default")
      (node (ref "D41") (pin "A") (pinfunction "A_A") (pintype "passive"))
      (node (ref "S41") (pin "P$1") (pinfunction "P$1_P$1") (pintype "bidirectional"))
    )
    (net (code "68") (name "Net-(D42-PadA)") (class "Default")
      (node (ref "D42") (pin "A") (pinfunction "A_A") (pintype "passive"))
      (node (ref "S42") (pin "P$1") (pinfunction "P$1_P$1") (pintype "bidirectional"))
    )
    (net (code "69") (name "Net-(D43-PadA)") (class "Default")
      (node (ref "D43") (pin "A") (pinfunction "A_A") (pintype "passive"))
      (node (ref "S43") (pin "P$1") (pinfunction "P$1_P$1") (pintype "bidirectional"))
    )
    (net (code "70") (name "Net-(D44-PadA)") (class "Default")
      (node (ref "D44") (pin "A") (pinfunction "A_A") (pintype "passive"))
      (node (ref "S44") (pin "P$1") (pinfunction "P$1_P$1") (pintype "bidirectional"))
    )
    (net (code "71") (name "Net-(D45-PadA)") (class "Default")
      (node (ref "D45") (pin "A") (pinfunction "A_A") (pintype "passive"))
      (node (ref "S45") (pin "P$1") (pinfunction "P$1_P$1") (pintype "bidirectional"))
    )
    (net (code "72") (name "Net-(D46-PadA)") (class "Default")
      (node (ref "D46") (pin "A") (pinfunction "A_A") (pintype "passive"))
      (node (ref "S46") (pin "P$1") (pinfunction "P$1_P$1") (pintype "bidirectional"))
    )
    (net (code "73") (name "Net-(D47-PadA)") (class "Default")
      (node (ref "D47") (pin "A") (pinfunction "A_A") (pintype "passive"))
      (node (ref "S47") (pin "P$1") (pinfunction "P$1_P$1") (pintype "bidirectional"))
    )
    (net (code "74") (name "Net-(D48-ANODE)") (class "Default")
      (node (ref "D48") (pin "1") (pinfunction "ANODE_1") (pintype "bidirectional"))
      (node (ref "F1") (pin "2") (pinfunction "2_2") (pintype "passive"))
    )
    (net (code "75") (name "Net-(F1-Pad1)") (class "Default")
      (node (ref "F1") (pin "1") (pinfunction "1_1") (pintype "passive"))
      (node (ref "USB1") (pin "A4/B9") (pinfunction "VBUS_A4/B9") (pintype "power_in"))
      (node (ref "USB1") (pin "B4/A9") (pinfunction "VBUS_B4/A9") (pintype "power_in"))
    )
    (net (code "76") (name "Net-(IC1-XTAL1)") (class "Default")
      (node (ref "C2") (pin "1") (pinfunction "1_1") (pintype "passive"))
      (node (ref "IC1") (pin "17") (pinfunction "XTAL1_17") (pintype "bidirectional"))
      (node (ref "Q1") (pin "3") (pinfunction "X2_3") (pintype "bidirectional"))
    )
    (net (code "77") (name "Net-(IC1-XTAL2)") (class "Default")
      (node (ref "C1") (pin "1") (pinfunction "1_1") (pintype "passive"))
      (node (ref "IC1") (pin "16") (pinfunction "XTAL2_16") (pintype "bidirectional"))
      (node (ref "Q1") (pin "1") (pinfunction "X1_1") (pintype "bidirectional"))
    )
    (net (code "78") (name "VCC") (class "Default")
      (node (ref "C4") (pin "1") (pinfunction "1_1") (pintype "passive"))
      (node (ref "C5") (pin "1") (pinfunction "1_1") (pintype "passive"))
      (node (ref "D48") (pin "2") (pinfunction "CATHODE_2") (pintype "bidirectional"))
      (node (ref "IC1") (pin "14") (pinfunction "VCC_14") (pintype "bidirectional"))
      (node (ref "IC1") (pin "2") (pinfunction "UVCC_2") (pintype "bidirectional"))
      (node (ref "IC1") (pin "24") (pinfunction "AVCC_24") (pintype "bidirectional"))
      (node (ref "IC1") (pin "34") (pinfunction "VCC1_34") (pintype "bidirectional"))
      (node (ref "IC1") (pin "44") (pinfunction "AVCC1_44") (pintype "bidirectional"))
      (node (ref "IC1") (pin "7") (pinfunction "VBUS_7") (pintype "bidirectional"))
      (node (ref "ISP1") (pin "2") (pinfunction "VCC_2") (pintype "bidirectional"))
      (node (ref "R1") (pin "2") (pinfunction "2_2") (pintype "passive"))
    )
    (net (code "79") (name "unconnected-(IC1-AREF-Pad42)") (class "Default")
      (node (ref "IC1") (pin "42") (pinfunction "AREF_42") (pintype "bidirectional"))
    )
    (net (code "80") (name "unconnected-(IC1-PB0(SS)-Pad8)") (class "Default")
      (node (ref "IC1") (pin "8") (pinfunction "PB0(SS)_8") (pintype "bidirectional"))
    )
    (net (code "81") (name "unconnected-(IC1-PB7(OC0A{slash}OC1C{slash}RTS)-Pad12)") (class "Default")
      (node (ref "IC1") (pin "12") (pinfunction "PB7(OC0A/OC1C/RTS)_12") (pintype "bidirectional"))
    )
    (net (code "82") (name "unconnected-(IC1-PD0(INT0{slash}OC0B{slash}SCL)-Pad18)") (class "Default")
      (node (ref "IC1") (pin "18") (pinfunction "PD0(INT0/OC0B/SCL)_18") (pintype "bidirectional"))
    )
    (net (code "83") (name "unconnected-(IC1-PE6(INT.6{slash}AIN0)-Pad1)") (class "Default")
      (node (ref "IC1") (pin "1") (pinfunction "PE6(INT.6/AIN0)_1") (pintype "bidirectional"))
    )
    (net (code "84") (name "unconnected-(IC1-PF0(ADC0)-Pad41)") (class "Default")
      (node (ref "IC1") (pin "41") (pinfunction "PF0(ADC0)_41") (pintype "bidirectional"))
    )
    (net (code "85") (name "unconnected-(IC1-PF1(ADC1)-Pad40)") (class "Default")
      (node (ref "IC1") (pin "40") (pinfunction "PF1(ADC1)_40") (pintype "bidirectional"))
    )
    (net (code "86") (name "unconnected-(IC1-PF7(ADC7(TDI)-Pad36)") (class "Default")
      (node (ref "IC1") (pin "36") (pinfunction "PF7(ADC7(TDI)_36") (pintype "bidirectional"))
    )
    (net (code "87") (name "unconnected-(IC2-IO0-Pad1)") (class "Default")
      (node (ref "IC2") (pin "1") (pinfunction "IO0_1") (pintype "bidirectional"))
    )
    (net (code "88") (name "unconnected-(IC2-IO1-Pad3)") (class "Default")
      (node (ref "IC2") (pin "3") (pinfunction "IO1_3") (pintype "bidirectional"))
    )
    (net (code "89") (name "unconnected-(USB1-CC1-PadA5)") (class "Default")
      (node (ref "USB1") (pin "A5") (pinfunction "CC1_A5") (pintype "bidirectional"))
    )
    (net (code "90") (name "unconnected-(USB1-CC2-PadB5)") (class "Default")
      (node (ref "USB1") (pin "B5") (pinfunction "CC2_B5") (pintype "bidirectional"))
    )
    (net (code "91") (name "unconnected-(USB1-SBU1-PadA8)") (class "Default")
      (node (ref "USB1") (pin "A8") (pinfunction "SBU1_A8") (pintype "bidirectional"))
    )
    (net (code "92") (name "unconnected-(USB1-SBU2-PadB8)") (class "Default")
      (node (ref "USB1") (pin "B8") (pinfunction "SBU2_B8") (pintype "bidirectional"))
    )
  )
)
